# Connectors_Sch.net
KiCad netlist of a schematic drawn in Altium Designer
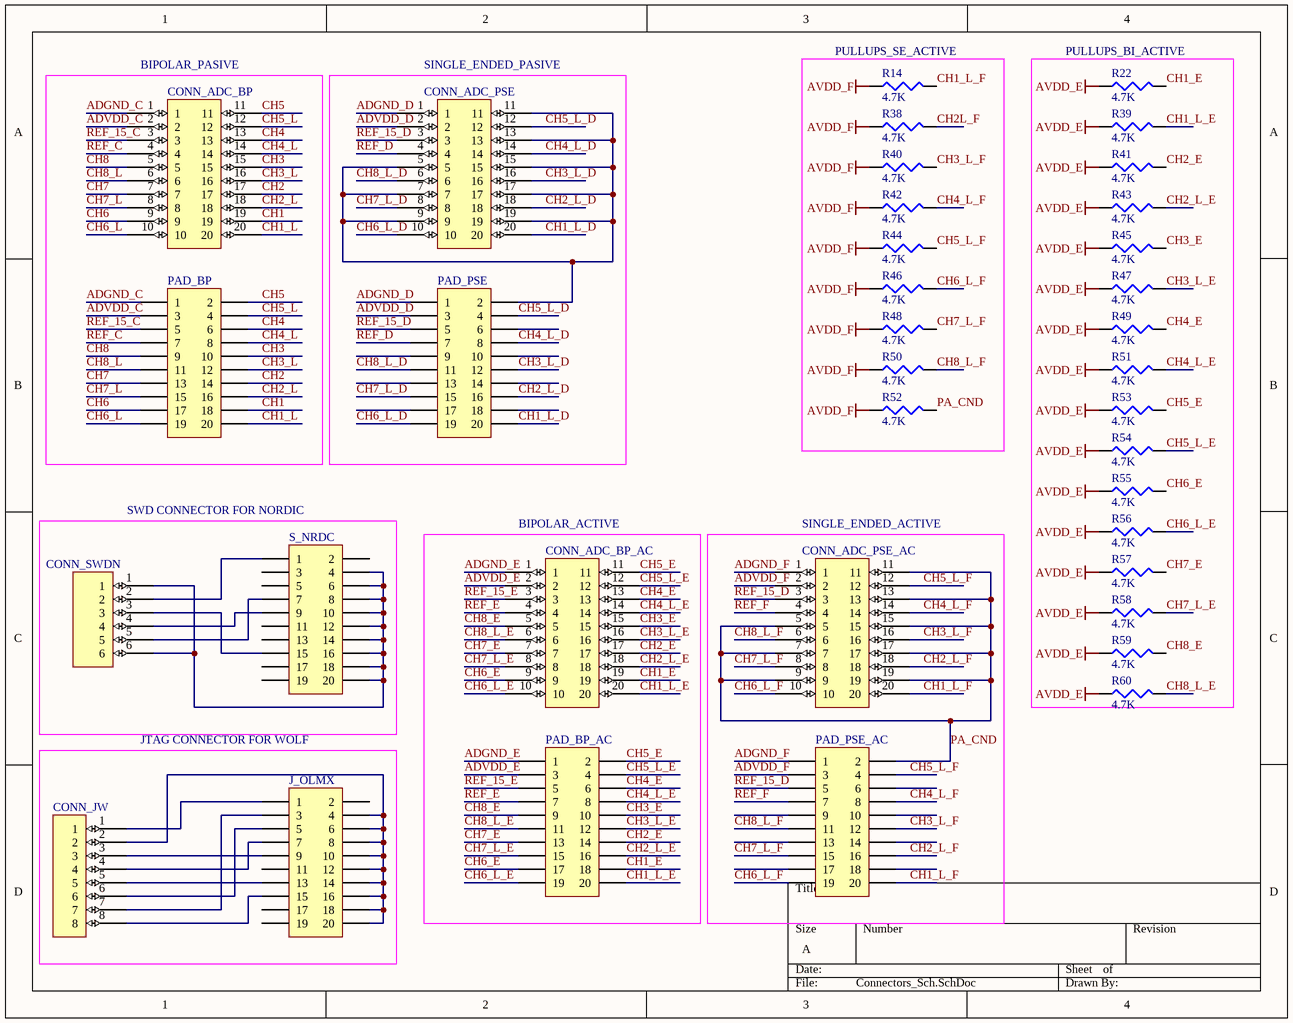
[diagram p0: Connectors_Sch.SchDoc]

(export (version "E")
  (design (tool "Eeschema 10.0.6"))
  (components
    (comp (ref "CONN_ADC_BP")
      (value "MOLEX_5051102091")
      (footprint "MOLEX_5051102091")
      (libsource (lib "Schlib1") (part "MOLEX_5051102091"))
    )
    (comp (ref "CONN_ADC_BP_AC")
      (value "MOLEX_5051102091")
      (footprint "MOLEX_5051102091")
      (libsource (lib "Schlib1") (part "MOLEX_5051102091"))
    )
    (comp (ref "CONN_ADC_PSE")
      (value "MOLEX_5051102091")
      (footprint "MOLEX_5051102091")
      (libsource (lib "Schlib1") (part "MOLEX_5051102091"))
    )
    (comp (ref "CONN_ADC_PSE_AC")
      (value "MOLEX_5051102091")
      (footprint "MOLEX_5051102091")
      (libsource (lib "Schlib1") (part "MOLEX_5051102091"))
    )
    (comp (ref "CONN_JW")
      (value "MOLEX_5051100892")
      (footprint "MOLEX_5051100892")
      (libsource (lib "Schlib1") (part "MOLEX_5051100892"))
    )
    (comp (ref "CONN_SWDN")
      (value "FFC & FPC Connectors 0.5 FPC ZIF BTM CONT EMBT PKG 6Ckt")
      (footprint "MOLEX_5051100692")
      (libsource (lib "Schlib2") (part "MOLEX_5051100692"))
    )
    (comp (ref "J_OLMX")
      (value "Header 10X2")
      (footprint "HDR2X10")
      (description "Header, 10-Pin, Dual row")
      (fields (field (name "PUBLISHER") "Altium Limited"))
      (libsource (lib "Miscellaneous Connectors") (part "Header 10X2"))
    )
    (comp (ref "PAD_BP")
      (value "Header 10X2")
      (footprint "HDR2X10")
      (description "Header, 10-Pin, Dual row")
      (fields (field (name "PUBLISHER") "Altium Limited"))
      (libsource (lib "Miscellaneous Connectors") (part "Header 10X2"))
    )
    (comp (ref "PAD_BP_AC")
      (value "Header 10X2")
      (footprint "HDR2X10")
      (description "Header, 10-Pin, Dual row")
      (fields (field (name "PUBLISHER") "Altium Limited"))
      (libsource (lib "Miscellaneous Connectors") (part "Header 10X2"))
    )
    (comp (ref "PAD_PSE")
      (value "Header 10X2")
      (footprint "HDR2X10")
      (description "Header, 10-Pin, Dual row")
      (fields (field (name "PUBLISHER") "Altium Limited"))
      (libsource (lib "Miscellaneous Connectors") (part "Header 10X2"))
    )
    (comp (ref "PAD_PSE_AC")
      (value "Header 10X2")
      (footprint "HDR2X10")
      (description "Header, 10-Pin, Dual row")
      (fields (field (name "PUBLISHER") "Altium Limited"))
      (libsource (lib "Miscellaneous Connectors") (part "Header 10X2"))
    )
    (comp (ref "R14")
      (value "4.7K")
      (footprint "0402")
      (description "Resistor")
      (fields (field (name "PUBLISHER") "Altium Limited"))
      (libsource (lib "Miscellaneous Devices") (part "Res3"))
    )
    (comp (ref "R22")
      (value "4.7K")
      (footprint "0402")
      (description "Resistor")
      (fields (field (name "PUBLISHER") "Altium Limited"))
      (libsource (lib "Miscellaneous Devices") (part "Res3"))
    )
    (comp (ref "R38")
      (value "4.7K")
      (footprint "0402")
      (description "Resistor")
      (fields (field (name "PUBLISHER") "Altium Limited"))
      (libsource (lib "Miscellaneous Devices") (part "Res3"))
    )
    (comp (ref "R39")
      (value "4.7K")
      (footprint "0402")
      (description "Resistor")
      (fields (field (name "PUBLISHER") "Altium Limited"))
      (libsource (lib "Miscellaneous Devices") (part "Res3"))
    )
    (comp (ref "R40")
      (value "4.7K")
      (footprint "0402")
      (description "Resistor")
      (fields (field (name "PUBLISHER") "Altium Limited"))
      (libsource (lib "Miscellaneous Devices") (part "Res3"))
    )
    (comp (ref "R41")
      (value "4.7K")
      (footprint "0402")
      (description "Resistor")
      (fields (field (name "PUBLISHER") "Altium Limited"))
      (libsource (lib "Miscellaneous Devices") (part "Res3"))
    )
    (comp (ref "R42")
      (value "4.7K")
      (footprint "0402")
      (description "Resistor")
      (fields (field (name "PUBLISHER") "Altium Limited"))
      (libsource (lib "Miscellaneous Devices") (part "Res3"))
    )
    (comp (ref "R43")
      (value "4.7K")
      (footprint "0402")
      (description "Resistor")
      (fields (field (name "PUBLISHER") "Altium Limited"))
      (libsource (lib "Miscellaneous Devices") (part "Res3"))
    )
    (comp (ref "R44")
      (value "4.7K")
      (footprint "0402")
      (description "Resistor")
      (fields (field (name "PUBLISHER") "Altium Limited"))
      (libsource (lib "Miscellaneous Devices") (part "Res3"))
    )
    (comp (ref "R45")
      (value "4.7K")
      (footprint "0402")
      (description "Resistor")
      (fields (field (name "PUBLISHER") "Altium Limited"))
      (libsource (lib "Miscellaneous Devices") (part "Res3"))
    )
    (comp (ref "R46")
      (value "4.7K")
      (footprint "0402")
      (description "Resistor")
      (fields (field (name "PUBLISHER") "Altium Limited"))
      (libsource (lib "Miscellaneous Devices") (part "Res3"))
    )
    (comp (ref "R47")
      (value "4.7K")
      (footprint "0402")
      (description "Resistor")
      (fields (field (name "PUBLISHER") "Altium Limited"))
      (libsource (lib "Miscellaneous Devices") (part "Res3"))
    )
    (comp (ref "R48")
      (value "4.7K")
      (footprint "0402")
      (description "Resistor")
      (fields (field (name "PUBLISHER") "Altium Limited"))
      (libsource (lib "Miscellaneous Devices") (part "Res3"))
    )
    (comp (ref "R49")
      (value "4.7K")
      (footprint "0402")
      (description "Resistor")
      (fields (field (name "PUBLISHER") "Altium Limited"))
      (libsource (lib "Miscellaneous Devices") (part "Res3"))
    )
    (comp (ref "R50")
      (value "4.7K")
      (footprint "0402")
      (description "Resistor")
      (fields (field (name "PUBLISHER") "Altium Limited"))
      (libsource (lib "Miscellaneous Devices") (part "Res3"))
    )
    (comp (ref "R51")
      (value "4.7K")
      (footprint "0402")
      (description "Resistor")
      (fields (field (name "PUBLISHER") "Altium Limited"))
      (libsource (lib "Miscellaneous Devices") (part "Res3"))
    )
    (comp (ref "R52")
      (value "4.7K")
      (footprint "0402")
      (description "Resistor")
      (fields (field (name "PUBLISHER") "Altium Limited"))
      (libsource (lib "Miscellaneous Devices") (part "Res3"))
    )
    (comp (ref "R53")
      (value "4.7K")
      (footprint "0402")
      (description "Resistor")
      (fields (field (name "PUBLISHER") "Altium Limited"))
      (libsource (lib "Miscellaneous Devices") (part "Res3"))
    )
    (comp (ref "R54")
      (value "4.7K")
      (footprint "0402")
      (description "Resistor")
      (fields (field (name "PUBLISHER") "Altium Limited"))
      (libsource (lib "Miscellaneous Devices") (part "Res3"))
    )
    (comp (ref "R55")
      (value "4.7K")
      (footprint "0402")
      (description "Resistor")
      (fields (field (name "PUBLISHER") "Altium Limited"))
      (libsource (lib "Miscellaneous Devices") (part "Res3"))
    )
    (comp (ref "R56")
      (value "4.7K")
      (footprint "0402")
      (description "Resistor")
      (fields (field (name "PUBLISHER") "Altium Limited"))
      (libsource (lib "Miscellaneous Devices") (part "Res3"))
    )
    (comp (ref "R57")
      (value "4.7K")
      (footprint "0402")
      (description "Resistor")
      (fields (field (name "PUBLISHER") "Altium Limited"))
      (libsource (lib "Miscellaneous Devices") (part "Res3"))
    )
    (comp (ref "R58")
      (value "4.7K")
      (footprint "0402")
      (description "Resistor")
      (fields (field (name "PUBLISHER") "Altium Limited"))
      (libsource (lib "Miscellaneous Devices") (part "Res3"))
    )
    (comp (ref "R59")
      (value "4.7K")
      (footprint "0402")
      (description "Resistor")
      (fields (field (name "PUBLISHER") "Altium Limited"))
      (libsource (lib "Miscellaneous Devices") (part "Res3"))
    )
    (comp (ref "R60")
      (value "4.7K")
      (footprint "0402")
      (description "Resistor")
      (fields (field (name "PUBLISHER") "Altium Limited"))
      (libsource (lib "Miscellaneous Devices") (part "Res3"))
    )
    (comp (ref "S_NRDC")
      (value "Header 10X2")
      (footprint "HDR2X10")
      (description "Header, 10-Pin, Dual row")
      (fields (field (name "PUBLISHER") "Altium Limited"))
      (libsource (lib "Miscellaneous Connectors") (part "Header 10X2"))
    )
  )
  (nets
    (net (code "1") (name "/ADGND_C") (class "Default")
      (node (ref "CONN_ADC_BP") (pin "1") (pinfunction "1_1") (pintype "bidirectional"))
      (node (ref "PAD_BP") (pin "1") (pinfunction "1_1") (pintype "passive"))
    )
    (net (code "2") (name "/ADGND_D") (class "Default")
      (node (ref "CONN_ADC_PSE") (pin "1") (pinfunction "1_1") (pintype "bidirectional"))
      (node (ref "PAD_PSE") (pin "1") (pinfunction "1_1") (pintype "passive"))
    )
    (net (code "3") (name "/ADGND_E") (class "Default")
      (node (ref "CONN_ADC_BP_AC") (pin "1") (pinfunction "1_1") (pintype "bidirectional"))
      (node (ref "PAD_BP_AC") (pin "1") (pinfunction "1_1") (pintype "passive"))
    )
    (net (code "4") (name "/ADGND_F") (class "Default")
      (node (ref "CONN_ADC_PSE_AC") (pin "1") (pinfunction "1_1") (pintype "bidirectional"))
      (node (ref "PAD_PSE_AC") (pin "1") (pinfunction "1_1") (pintype "passive"))
    )
    (net (code "5") (name "/ADVDD_C") (class "Default")
      (node (ref "CONN_ADC_BP") (pin "2") (pinfunction "2_2") (pintype "bidirectional"))
      (node (ref "PAD_BP") (pin "3") (pinfunction "3_3") (pintype "passive"))
    )
    (net (code "6") (name "/ADVDD_D") (class "Default")
      (node (ref "CONN_ADC_PSE") (pin "2") (pinfunction "2_2") (pintype "bidirectional"))
      (node (ref "PAD_PSE") (pin "3") (pinfunction "3_3") (pintype "passive"))
    )
    (net (code "7") (name "/ADVDD_E") (class "Default")
      (node (ref "CONN_ADC_BP_AC") (pin "2") (pinfunction "2_2") (pintype "bidirectional"))
      (node (ref "PAD_BP_AC") (pin "3") (pinfunction "3_3") (pintype "passive"))
    )
    (net (code "8") (name "/ADVDD_F") (class "Default")
      (node (ref "CONN_ADC_PSE_AC") (pin "2") (pinfunction "2_2") (pintype "bidirectional"))
      (node (ref "PAD_PSE_AC") (pin "3") (pinfunction "3_3") (pintype "passive"))
    )
    (net (code "9") (name "/CH1") (class "Default")
      (node (ref "CONN_ADC_BP") (pin "19") (pinfunction "19_19") (pintype "bidirectional"))
      (node (ref "PAD_BP") (pin "18") (pinfunction "18_18") (pintype "passive"))
    )
    (net (code "10") (name "/CH1_E") (class "Default")
      (node (ref "CONN_ADC_BP_AC") (pin "19") (pinfunction "19_19") (pintype "bidirectional"))
      (node (ref "PAD_BP_AC") (pin "18") (pinfunction "18_18") (pintype "passive"))
      (node (ref "R22") (pin "2") (pinfunction "2_2") (pintype "passive"))
    )
    (net (code "11") (name "/CH1_L") (class "Default")
      (node (ref "CONN_ADC_BP") (pin "20") (pinfunction "20_20") (pintype "bidirectional"))
      (node (ref "PAD_BP") (pin "20") (pinfunction "20_20") (pintype "passive"))
    )
    (net (code "12") (name "/CH1_L_D") (class "Default")
      (node (ref "CONN_ADC_PSE") (pin "20") (pinfunction "20_20") (pintype "bidirectional"))
      (node (ref "PAD_PSE") (pin "20") (pinfunction "20_20") (pintype "passive"))
    )
    (net (code "13") (name "/CH1_L_E") (class "Default")
      (node (ref "CONN_ADC_BP_AC") (pin "20") (pinfunction "20_20") (pintype "bidirectional"))
      (node (ref "PAD_BP_AC") (pin "20") (pinfunction "20_20") (pintype "passive"))
      (node (ref "R39") (pin "2") (pinfunction "2_2") (pintype "passive"))
    )
    (net (code "14") (name "/CH1_L_F") (class "Default")
      (node (ref "CONN_ADC_PSE_AC") (pin "20") (pinfunction "20_20") (pintype "bidirectional"))
      (node (ref "PAD_PSE_AC") (pin "20") (pinfunction "20_20") (pintype "passive"))
      (node (ref "R14") (pin "2") (pinfunction "2_2") (pintype "passive"))
    )
    (net (code "15") (name "/CH2") (class "Default")
      (node (ref "CONN_ADC_BP") (pin "17") (pinfunction "17_17") (pintype "bidirectional"))
      (node (ref "PAD_BP") (pin "14") (pinfunction "14_14") (pintype "passive"))
    )
    (net (code "16") (name "/CH2L_F") (class "Default")
      (node (ref "R38") (pin "2") (pinfunction "2_2") (pintype "passive"))
    )
    (net (code "17") (name "/CH2_E") (class "Default")
      (node (ref "CONN_ADC_BP_AC") (pin "17") (pinfunction "17_17") (pintype "bidirectional"))
      (node (ref "PAD_BP_AC") (pin "14") (pinfunction "14_14") (pintype "passive"))
      (node (ref "R41") (pin "2") (pinfunction "2_2") (pintype "passive"))
    )
    (net (code "18") (name "/CH2_L") (class "Default")
      (node (ref "CONN_ADC_BP") (pin "18") (pinfunction "18_18") (pintype "bidirectional"))
      (node (ref "PAD_BP") (pin "16") (pinfunction "16_16") (pintype "passive"))
    )
    (net (code "19") (name "/CH2_L_D") (class "Default")
      (node (ref "CONN_ADC_PSE") (pin "18") (pinfunction "18_18") (pintype "bidirectional"))
      (node (ref "PAD_PSE") (pin "16") (pinfunction "16_16") (pintype "passive"))
    )
    (net (code "20") (name "/CH2_L_E") (class "Default")
      (node (ref "CONN_ADC_BP_AC") (pin "18") (pinfunction "18_18") (pintype "bidirectional"))
      (node (ref "PAD_BP_AC") (pin "16") (pinfunction "16_16") (pintype "passive"))
      (node (ref "R43") (pin "2") (pinfunction "2_2") (pintype "passive"))
    )
    (net (code "21") (name "/CH2_L_F") (class "Default")
      (node (ref "CONN_ADC_PSE_AC") (pin "18") (pinfunction "18_18") (pintype "bidirectional"))
      (node (ref "PAD_PSE_AC") (pin "16") (pinfunction "16_16") (pintype "passive"))
    )
    (net (code "22") (name "/CH3") (class "Default")
      (node (ref "CONN_ADC_BP") (pin "15") (pinfunction "15_15") (pintype "bidirectional"))
      (node (ref "PAD_BP") (pin "10") (pinfunction "10_10") (pintype "passive"))
    )
    (net (code "23") (name "/CH3_E") (class "Default")
      (node (ref "CONN_ADC_BP_AC") (pin "15") (pinfunction "15_15") (pintype "bidirectional"))
      (node (ref "PAD_BP_AC") (pin "10") (pinfunction "10_10") (pintype "passive"))
      (node (ref "R45") (pin "2") (pinfunction "2_2") (pintype "passive"))
    )
    (net (code "24") (name "/CH3_L") (class "Default")
      (node (ref "CONN_ADC_BP") (pin "16") (pinfunction "16_16") (pintype "bidirectional"))
      (node (ref "PAD_BP") (pin "12") (pinfunction "12_12") (pintype "passive"))
    )
    (net (code "25") (name "/CH3_L_D") (class "Default")
      (node (ref "CONN_ADC_PSE") (pin "16") (pinfunction "16_16") (pintype "bidirectional"))
      (node (ref "PAD_PSE") (pin "12") (pinfunction "12_12") (pintype "passive"))
    )
    (net (code "26") (name "/CH3_L_E") (class "Default")
      (node (ref "CONN_ADC_BP_AC") (pin "16") (pinfunction "16_16") (pintype "bidirectional"))
      (node (ref "PAD_BP_AC") (pin "12") (pinfunction "12_12") (pintype "passive"))
      (node (ref "R47") (pin "2") (pinfunction "2_2") (pintype "passive"))
    )
    (net (code "27") (name "/CH3_L_F") (class "Default")
      (node (ref "CONN_ADC_PSE_AC") (pin "16") (pinfunction "16_16") (pintype "bidirectional"))
      (node (ref "PAD_PSE_AC") (pin "12") (pinfunction "12_12") (pintype "passive"))
      (node (ref "R40") (pin "2") (pinfunction "2_2") (pintype "passive"))
    )
    (net (code "28") (name "/CH4") (class "Default")
      (node (ref "CONN_ADC_BP") (pin "13") (pinfunction "13_13") (pintype "bidirectional"))
      (node (ref "PAD_BP") (pin "6") (pinfunction "6_6") (pintype "passive"))
    )
    (net (code "29") (name "/CH4_E") (class "Default")
      (node (ref "CONN_ADC_BP_AC") (pin "13") (pinfunction "13_13") (pintype "bidirectional"))
      (node (ref "PAD_BP_AC") (pin "6") (pinfunction "6_6") (pintype "passive"))
      (node (ref "R49") (pin "2") (pinfunction "2_2") (pintype "passive"))
    )
    (net (code "30") (name "/CH4_L") (class "Default")
      (node (ref "CONN_ADC_BP") (pin "14") (pinfunction "14_14") (pintype "bidirectional"))
      (node (ref "PAD_BP") (pin "8") (pinfunction "8_8") (pintype "passive"))
    )
    (net (code "31") (name "/CH4_L_D") (class "Default")
      (node (ref "CONN_ADC_PSE") (pin "14") (pinfunction "14_14") (pintype "bidirectional"))
      (node (ref "PAD_PSE") (pin "8") (pinfunction "8_8") (pintype "passive"))
    )
    (net (code "32") (name "/CH4_L_E") (class "Default")
      (node (ref "CONN_ADC_BP_AC") (pin "14") (pinfunction "14_14") (pintype "bidirectional"))
      (node (ref "PAD_BP_AC") (pin "8") (pinfunction "8_8") (pintype "passive"))
      (node (ref "R51") (pin "2") (pinfunction "2_2") (pintype "passive"))
    )
    (net (code "33") (name "/CH4_L_F") (class "Default")
      (node (ref "CONN_ADC_PSE_AC") (pin "14") (pinfunction "14_14") (pintype "bidirectional"))
      (node (ref "PAD_PSE_AC") (pin "8") (pinfunction "8_8") (pintype "passive"))
      (node (ref "R42") (pin "2") (pinfunction "2_2") (pintype "passive"))
    )
    (net (code "34") (name "/CH5") (class "Default")
      (node (ref "CONN_ADC_BP") (pin "11") (pinfunction "11_11") (pintype "bidirectional"))
      (node (ref "PAD_BP") (pin "2") (pinfunction "2_2") (pintype "passive"))
    )
    (net (code "35") (name "/CH5_E") (class "Default")
      (node (ref "CONN_ADC_BP_AC") (pin "11") (pinfunction "11_11") (pintype "bidirectional"))
      (node (ref "PAD_BP_AC") (pin "2") (pinfunction "2_2") (pintype "passive"))
      (node (ref "R53") (pin "2") (pinfunction "2_2") (pintype "passive"))
    )
    (net (code "36") (name "/CH5_L") (class "Default")
      (node (ref "CONN_ADC_BP") (pin "12") (pinfunction "12_12") (pintype "bidirectional"))
      (node (ref "PAD_BP") (pin "4") (pinfunction "4_4") (pintype "passive"))
    )
    (net (code "37") (name "/CH5_L_D") (class "Default")
      (node (ref "CONN_ADC_PSE") (pin "12") (pinfunction "12_12") (pintype "bidirectional"))
      (node (ref "PAD_PSE") (pin "4") (pinfunction "4_4") (pintype "passive"))
    )
    (net (code "38") (name "/CH5_L_E") (class "Default")
      (node (ref "CONN_ADC_BP_AC") (pin "12") (pinfunction "12_12") (pintype "bidirectional"))
      (node (ref "PAD_BP_AC") (pin "4") (pinfunction "4_4") (pintype "passive"))
      (node (ref "R54") (pin "2") (pinfunction "2_2") (pintype "passive"))
    )
    (net (code "39") (name "/CH5_L_F") (class "Default")
      (node (ref "CONN_ADC_PSE_AC") (pin "12") (pinfunction "12_12") (pintype "bidirectional"))
      (node (ref "PAD_PSE_AC") (pin "4") (pinfunction "4_4") (pintype "passive"))
      (node (ref "R44") (pin "2") (pinfunction "2_2") (pintype "passive"))
    )
    (net (code "40") (name "/CH6") (class "Default")
      (node (ref "CONN_ADC_BP") (pin "9") (pinfunction "9_9") (pintype "bidirectional"))
      (node (ref "PAD_BP") (pin "17") (pinfunction "17_17") (pintype "passive"))
    )
    (net (code "41") (name "/CH6_E") (class "Default")
      (node (ref "CONN_ADC_BP_AC") (pin "9") (pinfunction "9_9") (pintype "bidirectional"))
      (node (ref "PAD_BP_AC") (pin "17") (pinfunction "17_17") (pintype "passive"))
      (node (ref "R55") (pin "2") (pinfunction "2_2") (pintype "passive"))
    )
    (net (code "42") (name "/CH6_L") (class "Default")
      (node (ref "CONN_ADC_BP") (pin "10") (pinfunction "10_10") (pintype "bidirectional"))
      (node (ref "PAD_BP") (pin "19") (pinfunction "19_19") (pintype "passive"))
    )
    (net (code "43") (name "/CH6_L_D") (class "Default")
      (node (ref "CONN_ADC_PSE") (pin "10") (pinfunction "10_10") (pintype "bidirectional"))
      (node (ref "PAD_PSE") (pin "19") (pinfunction "19_19") (pintype "passive"))
    )
    (net (code "44") (name "/CH6_L_E") (class "Default")
      (node (ref "CONN_ADC_BP_AC") (pin "10") (pinfunction "10_10") (pintype "bidirectional"))
      (node (ref "PAD_BP_AC") (pin "19") (pinfunction "19_19") (pintype "passive"))
      (node (ref "R56") (pin "2") (pinfunction "2_2") (pintype "passive"))
    )
    (net (code "45") (name "/CH6_L_F") (class "Default")
      (node (ref "CONN_ADC_PSE_AC") (pin "10") (pinfunction "10_10") (pintype "bidirectional"))
      (node (ref "PAD_PSE_AC") (pin "19") (pinfunction "19_19") (pintype "passive"))
      (node (ref "R46") (pin "2") (pinfunction "2_2") (pintype "passive"))
    )
    (net (code "46") (name "/CH7") (class "Default")
      (node (ref "CONN_ADC_BP") (pin "7") (pinfunction "7_7") (pintype "bidirectional"))
      (node (ref "PAD_BP") (pin "13") (pinfunction "13_13") (pintype "passive"))
    )
    (net (code "47") (name "/CH7_E") (class "Default")
      (node (ref "CONN_ADC_BP_AC") (pin "7") (pinfunction "7_7") (pintype "bidirectional"))
      (node (ref "PAD_BP_AC") (pin "13") (pinfunction "13_13") (pintype "passive"))
      (node (ref "R57") (pin "2") (pinfunction "2_2") (pintype "passive"))
    )
    (net (code "48") (name "/CH7_L") (class "Default")
      (node (ref "CONN_ADC_BP") (pin "8") (pinfunction "8_8") (pintype "bidirectional"))
      (node (ref "PAD_BP") (pin "15") (pinfunction "15_15") (pintype "passive"))
    )
    (net (code "49") (name "/CH7_L_D") (class "Default")
      (node (ref "CONN_ADC_PSE") (pin "8") (pinfunction "8_8") (pintype "bidirectional"))
      (node (ref "PAD_PSE") (pin "15") (pinfunction "15_15") (pintype "passive"))
    )
    (net (code "50") (name "/CH7_L_E") (class "Default")
      (node (ref "CONN_ADC_BP_AC") (pin "8") (pinfunction "8_8") (pintype "bidirectional"))
      (node (ref "PAD_BP_AC") (pin "15") (pinfunction "15_15") (pintype "passive"))
      (node (ref "R58") (pin "2") (pinfunction "2_2") (pintype "passive"))
    )
    (net (code "51") (name "/CH7_L_F") (class "Default")
      (node (ref "CONN_ADC_PSE_AC") (pin "8") (pinfunction "8_8") (pintype "bidirectional"))
      (node (ref "PAD_PSE_AC") (pin "15") (pinfunction "15_15") (pintype "passive"))
      (node (ref "R48") (pin "2") (pinfunction "2_2") (pintype "passive"))
    )
    (net (code "52") (name "/CH8") (class "Default")
      (node (ref "CONN_ADC_BP") (pin "5") (pinfunction "5_5") (pintype "bidirectional"))
      (node (ref "PAD_BP") (pin "9") (pinfunction "9_9") (pintype "passive"))
    )
    (net (code "53") (name "/CH8_E") (class "Default")
      (node (ref "CONN_ADC_BP_AC") (pin "5") (pinfunction "5_5") (pintype "bidirectional"))
      (node (ref "PAD_BP_AC") (pin "9") (pinfunction "9_9") (pintype "passive"))
      (node (ref "R59") (pin "2") (pinfunction "2_2") (pintype "passive"))
    )
    (net (code "54") (name "/CH8_L") (class "Default")
      (node (ref "CONN_ADC_BP") (pin "6") (pinfunction "6_6") (pintype "bidirectional"))
      (node (ref "PAD_BP") (pin "11") (pinfunction "11_11") (pintype "passive"))
    )
    (net (code "55") (name "/CH8_L_D") (class "Default")
      (node (ref "CONN_ADC_PSE") (pin "6") (pinfunction "6_6") (pintype "bidirectional"))
      (node (ref "PAD_PSE") (pin "11") (pinfunction "11_11") (pintype "passive"))
    )
    (net (code "56") (name "/CH8_L_E") (class "Default")
      (node (ref "CONN_ADC_BP_AC") (pin "6") (pinfunction "6_6") (pintype "bidirectional"))
      (node (ref "PAD_BP_AC") (pin "11") (pinfunction "11_11") (pintype "passive"))
      (node (ref "R60") (pin "2") (pinfunction "2_2") (pintype "passive"))
    )
    (net (code "57") (name "/CH8_L_F") (class "Default")
      (node (ref "CONN_ADC_PSE_AC") (pin "6") (pinfunction "6_6") (pintype "bidirectional"))
      (node (ref "PAD_PSE_AC") (pin "11") (pinfunction "11_11") (pintype "passive"))
      (node (ref "R50") (pin "2") (pinfunction "2_2") (pintype "passive"))
    )
    (net (code "58") (name "/PA_CND") (class "Default")
      (node (ref "CONN_ADC_PSE_AC") (pin "11") (pinfunction "11_11") (pintype "bidirectional"))
      (node (ref "CONN_ADC_PSE_AC") (pin "13") (pinfunction "13_13") (pintype "bidirectional"))
      (node (ref "CONN_ADC_PSE_AC") (pin "15") (pinfunction "15_15") (pintype "bidirectional"))
      (node (ref "CONN_ADC_PSE_AC") (pin "17") (pinfunction "17_17") (pintype "bidirectional"))
      (node (ref "CONN_ADC_PSE_AC") (pin "19") (pinfunction "19_19") (pintype "bidirectional"))
      (node (ref "CONN_ADC_PSE_AC") (pin "5") (pinfunction "5_5") (pintype "bidirectional"))
      (node (ref "CONN_ADC_PSE_AC") (pin "7") (pinfunction "7_7") (pintype "bidirectional"))
      (node (ref "CONN_ADC_PSE_AC") (pin "9") (pinfunction "9_9") (pintype "bidirectional"))
      (node (ref "PAD_PSE_AC") (pin "2") (pinfunction "2_2") (pintype "passive"))
      (node (ref "R52") (pin "2") (pinfunction "2_2") (pintype "passive"))
    )
    (net (code "59") (name "/REF_15_C") (class "Default")
      (node (ref "CONN_ADC_BP") (pin "3") (pinfunction "3_3") (pintype "bidirectional"))
      (node (ref "PAD_BP") (pin "5") (pinfunction "5_5") (pintype "passive"))
    )
    (net (code "60") (name "/REF_15_D") (class "Default")
      (node (ref "CONN_ADC_PSE") (pin "3") (pinfunction "3_3") (pintype "bidirectional"))
      (node (ref "CONN_ADC_PSE_AC") (pin "3") (pinfunction "3_3") (pintype "bidirectional"))
      (node (ref "PAD_PSE") (pin "5") (pinfunction "5_5") (pintype "passive"))
      (node (ref "PAD_PSE_AC") (pin "5") (pinfunction "5_5") (pintype "passive"))
    )
    (net (code "61") (name "/REF_15_E") (class "Default")
      (node (ref "CONN_ADC_BP_AC") (pin "3") (pinfunction "3_3") (pintype "bidirectional"))
      (node (ref "PAD_BP_AC") (pin "5") (pinfunction "5_5") (pintype "passive"))
    )
    (net (code "62") (name "/REF_C") (class "Default")
      (node (ref "CONN_ADC_BP") (pin "4") (pinfunction "4_4") (pintype "bidirectional"))
      (node (ref "PAD_BP") (pin "7") (pinfunction "7_7") (pintype "passive"))
    )
    (net (code "63") (name "/REF_D") (class "Default")
      (node (ref "CONN_ADC_PSE") (pin "4") (pinfunction "4_4") (pintype "bidirectional"))
      (node (ref "PAD_PSE") (pin "7") (pinfunction "7_7") (pintype "passive"))
    )
    (net (code "64") (name "/REF_E") (class "Default")
      (node (ref "CONN_ADC_BP_AC") (pin "4") (pinfunction "4_4") (pintype "bidirectional"))
      (node (ref "PAD_BP_AC") (pin "7") (pinfunction "7_7") (pintype "passive"))
    )
    (net (code "65") (name "/REF_F") (class "Default")
      (node (ref "CONN_ADC_PSE_AC") (pin "4") (pinfunction "4_4") (pintype "bidirectional"))
      (node (ref "PAD_PSE_AC") (pin "7") (pinfunction "7_7") (pintype "passive"))
    )
    (net (code "66") (name "AVDD_E") (class "Default")
      (node (ref "R22") (pin "1") (pinfunction "1_1") (pintype "passive"))
      (node (ref "R39") (pin "1") (pinfunction "1_1") (pintype "passive"))
      (node (ref "R41") (pin "1") (pinfunction "1_1") (pintype "passive"))
      (node (ref "R43") (pin "1") (pinfunction "1_1") (pintype "passive"))
      (node (ref "R45") (pin "1") (pinfunction "1_1") (pintype "passive"))
      (node (ref "R47") (pin "1") (pinfunction "1_1") (pintype "passive"))
      (node (ref "R49") (pin "1") (pinfunction "1_1") (pintype "passive"))
      (node (ref "R51") (pin "1") (pinfunction "1_1") (pintype "passive"))
      (node (ref "R53") (pin "1") (pinfunction "1_1") (pintype "passive"))
      (node (ref "R54") (pin "1") (pinfunction "1_1") (pintype "passive"))
      (node (ref "R55") (pin "1") (pinfunction "1_1") (pintype "passive"))
      (node (ref "R56") (pin "1") (pinfunction "1_1") (pintype "passive"))
      (node (ref "R57") (pin "1") (pinfunction "1_1") (pintype "passive"))
      (node (ref "R58") (pin "1") (pinfunction "1_1") (pintype "passive"))
      (node (ref "R59") (pin "1") (pinfunction "1_1") (pintype "passive"))
      (node (ref "R60") (pin "1") (pinfunction "1_1") (pintype "passive"))
    )
    (net (code "67") (name "AVDD_F") (class "Default")
      (node (ref "R14") (pin "1") (pinfunction "1_1") (pintype "passive"))
      (node (ref "R38") (pin "1") (pinfunction "1_1") (pintype "passive"))
      (node (ref "R40") (pin "1") (pinfunction "1_1") (pintype "passive"))
      (node (ref "R42") (pin "1") (pinfunction "1_1") (pintype "passive"))
      (node (ref "R44") (pin "1") (pinfunction "1_1") (pintype "passive"))
      (node (ref "R46") (pin "1") (pinfunction "1_1") (pintype "passive"))
      (node (ref "R48") (pin "1") (pinfunction "1_1") (pintype "passive"))
      (node (ref "R50") (pin "1") (pinfunction "1_1") (pintype "passive"))
      (node (ref "R52") (pin "1") (pinfunction "1_1") (pintype "passive"))
    )
    (net (code "68") (name "Net-(CONN_ADC_PSE-Pad11)") (class "Default")
      (node (ref "CONN_ADC_PSE") (pin "11") (pinfunction "11_11") (pintype "bidirectional"))
      (node (ref "CONN_ADC_PSE") (pin "13") (pinfunction "13_13") (pintype "bidirectional"))
      (node (ref "CONN_ADC_PSE") (pin "15") (pinfunction "15_15") (pintype "bidirectional"))
      (node (ref "CONN_ADC_PSE") (pin "17") (pinfunction "17_17") (pintype "bidirectional"))
      (node (ref "CONN_ADC_PSE") (pin "19") (pinfunction "19_19") (pintype "bidirectional"))
      (node (ref "CONN_ADC_PSE") (pin "5") (pinfunction "5_5") (pintype "bidirectional"))
      (node (ref "CONN_ADC_PSE") (pin "7") (pinfunction "7_7") (pintype "bidirectional"))
      (node (ref "CONN_ADC_PSE") (pin "9") (pinfunction "9_9") (pintype "bidirectional"))
      (node (ref "PAD_PSE") (pin "2") (pinfunction "2_2") (pintype "passive"))
    )
    (net (code "69") (name "Net-(CONN_JW-Pad1)") (class "Default")
      (node (ref "CONN_JW") (pin "1") (pinfunction "1_1") (pintype "bidirectional"))
      (node (ref "J_OLMX") (pin "1") (pinfunction "1_1") (pintype "passive"))
    )
    (net (code "70") (name "Net-(CONN_JW-Pad2)") (class "Default")
      (node (ref "CONN_JW") (pin "2") (pinfunction "2_2") (pintype "bidirectional"))
      (node (ref "J_OLMX") (pin "10") (pinfunction "10_10") (pintype "passive"))
      (node (ref "J_OLMX") (pin "12") (pinfunction "12_12") (pintype "passive"))
      (node (ref "J_OLMX") (pin "14") (pinfunction "14_14") (pintype "passive"))
      (node (ref "J_OLMX") (pin "16") (pinfunction "16_16") (pintype "passive"))
      (node (ref "J_OLMX") (pin "18") (pinfunction "18_18") (pintype "passive"))
      (node (ref "J_OLMX") (pin "20") (pinfunction "20_20") (pintype "passive"))
      (node (ref "J_OLMX") (pin "4") (pinfunction "4_4") (pintype "passive"))
      (node (ref "J_OLMX") (pin "6") (pinfunction "6_6") (pintype "passive"))
      (node (ref "J_OLMX") (pin "8") (pinfunction "8_8") (pintype "passive"))
    )
    (net (code "71") (name "Net-(CONN_JW-Pad3)") (class "Default")
      (node (ref "CONN_JW") (pin "3") (pinfunction "3_3") (pintype "bidirectional"))
      (node (ref "J_OLMX") (pin "9") (pinfunction "9_9") (pintype "passive"))
    )
    (net (code "72") (name "Net-(CONN_JW-Pad4)") (class "Default")
      (node (ref "CONN_JW") (pin "4") (pinfunction "4_4") (pintype "bidirectional"))
      (node (ref "J_OLMX") (pin "7") (pinfunction "7_7") (pintype "passive"))
    )
    (net (code "73") (name "Net-(CONN_JW-Pad5)") (class "Default")
      (node (ref "CONN_JW") (pin "5") (pinfunction "5_5") (pintype "bidirectional"))
      (node (ref "J_OLMX") (pin "13") (pinfunction "13_13") (pintype "passive"))
    )
    (net (code "74") (name "Net-(CONN_JW-Pad6)") (class "Default")
      (node (ref "CONN_JW") (pin "6") (pinfunction "6_6") (pintype "bidirectional"))
      (node (ref "J_OLMX") (pin "5") (pinfunction "5_5") (pintype "passive"))
    )
    (net (code "75") (name "Net-(CONN_JW-Pad7)") (class "Default")
      (node (ref "CONN_JW") (pin "7") (pinfunction "7_7") (pintype "bidirectional"))
      (node (ref "J_OLMX") (pin "3") (pinfunction "3_3") (pintype "passive"))
    )
    (net (code "76") (name "Net-(CONN_JW-Pad8)") (class "Default")
      (node (ref "CONN_JW") (pin "8") (pinfunction "8_8") (pintype "bidirectional"))
      (node (ref "J_OLMX") (pin "15") (pinfunction "15_15") (pintype "passive"))
    )
    (net (code "77") (name "Net-(CONN_SWDN-Pad1)") (class "Default")
      (node (ref "CONN_SWDN") (pin "1") (pinfunction "1_1") (pintype "bidirectional"))
      (node (ref "CONN_SWDN") (pin "6") (pinfunction "6_6") (pintype "bidirectional"))
      (node (ref "S_NRDC") (pin "10") (pinfunction "10_10") (pintype "passive"))
      (node (ref "S_NRDC") (pin "12") (pinfunction "12_12") (pintype "passive"))
      (node (ref "S_NRDC") (pin "14") (pinfunction "14_14") (pintype "passive"))
      (node (ref "S_NRDC") (pin "16") (pinfunction "16_16") (pintype "passive"))
      (node (ref "S_NRDC") (pin "18") (pinfunction "18_18") (pintype "passive"))
      (node (ref "S_NRDC") (pin "20") (pinfunction "20_20") (pintype "passive"))
      (node (ref "S_NRDC") (pin "4") (pinfunction "4_4") (pintype "passive"))
      (node (ref "S_NRDC") (pin "6") (pinfunction "6_6") (pintype "passive"))
      (node (ref "S_NRDC") (pin "8") (pinfunction "8_8") (pintype "passive"))
    )
    (net (code "78") (name "Net-(CONN_SWDN-Pad2)") (class "Default")
      (node (ref "CONN_SWDN") (pin "2") (pinfunction "2_2") (pintype "bidirectional"))
      (node (ref "S_NRDC") (pin "1") (pinfunction "1_1") (pintype "passive"))
    )
    (net (code "79") (name "Net-(CONN_SWDN-Pad3)") (class "Default")
      (node (ref "CONN_SWDN") (pin "3") (pinfunction "3_3") (pintype "bidirectional"))
      (node (ref "S_NRDC") (pin "15") (pinfunction "15_15") (pintype "passive"))
    )
    (net (code "80") (name "Net-(CONN_SWDN-Pad4)") (class "Default")
      (node (ref "CONN_SWDN") (pin "4") (pinfunction "4_4") (pintype "bidirectional"))
      (node (ref "S_NRDC") (pin "9") (pinfunction "9_9") (pintype "passive"))
    )
    (net (code "81") (name "Net-(CONN_SWDN-Pad5)") (class "Default")
      (node (ref "CONN_SWDN") (pin "5") (pinfunction "5_5") (pintype "bidirectional"))
      (node (ref "S_NRDC") (pin "7") (pinfunction "7_7") (pintype "passive"))
    )
    (net (code "82") (name "unconnected-(J_OLMX-Pad2)") (class "Default")
      (node (ref "J_OLMX") (pin "2") (pinfunction "2_2") (pintype "passive"))
    )
    (net (code "83") (name "unconnected-(J_OLMX-Pad11)") (class "Default")
      (node (ref "J_OLMX") (pin "11") (pinfunction "11_11") (pintype "passive"))
    )
    (net (code "84") (name "unconnected-(J_OLMX-Pad17)") (class "Default")
      (node (ref "J_OLMX") (pin "17") (pinfunction "17_17") (pintype "passive"))
    )
    (net (code "85") (name "unconnected-(J_OLMX-Pad19)") (class "Default")
      (node (ref "J_OLMX") (pin "19") (pinfunction "19_19") (pintype "passive"))
    )
    (net (code "86") (name "unconnected-(PAD_PSE-Pad6)") (class "Default")
      (node (ref "PAD_PSE") (pin "6") (pinfunction "6_6") (pintype "passive"))
    )
    (net (code "87") (name "unconnected-(PAD_PSE-Pad9)") (class "Default")
      (node (ref "PAD_PSE") (pin "9") (pinfunction "9_9") (pintype "passive"))
    )
    (net (code "88") (name "unconnected-(PAD_PSE-Pad10)") (class "Default")
      (node (ref "PAD_PSE") (pin "10") (pinfunction "10_10") (pintype "passive"))
    )
    (net (code "89") (name "unconnected-(PAD_PSE-Pad13)") (class "Default")
      (node (ref "PAD_PSE") (pin "13") (pinfunction "13_13") (pintype "passive"))
    )
    (net (code "90") (name "unconnected-(PAD_PSE-Pad14)") (class "Default")
      (node (ref "PAD_PSE") (pin "14") (pinfunction "14_14") (pintype "passive"))
    )
    (net (code "91") (name "unconnected-(PAD_PSE-Pad17)") (class "Default")
      (node (ref "PAD_PSE") (pin "17") (pinfunction "17_17") (pintype "passive"))
    )
    (net (code "92") (name "unconnected-(PAD_PSE-Pad18)") (class "Default")
      (node (ref "PAD_PSE") (pin "18") (pinfunction "18_18") (pintype "passive"))
    )
    (net (code "93") (name "unconnected-(PAD_PSE_AC-Pad6)") (class "Default")
      (node (ref "PAD_PSE_AC") (pin "6") (pinfunction "6_6") (pintype "passive"))
    )
    (net (code "94") (name "unconnected-(PAD_PSE_AC-Pad9)") (class "Default")
      (node (ref "PAD_PSE_AC") (pin "9") (pinfunction "9_9") (pintype "passive"))
    )
    (net (code "95") (name "unconnected-(PAD_PSE_AC-Pad10)") (class "Default")
      (node (ref "PAD_PSE_AC") (pin "10") (pinfunction "10_10") (pintype "passive"))
    )
    (net (code "96") (name "unconnected-(PAD_PSE_AC-Pad13)") (class "Default")
      (node (ref "PAD_PSE_AC") (pin "13") (pinfunction "13_13") (pintype "passive"))
    )
    (net (code "97") (name "unconnected-(PAD_PSE_AC-Pad14)") (class "Default")
      (node (ref "PAD_PSE_AC") (pin "14") (pinfunction "14_14") (pintype "passive"))
    )
    (net (code "98") (name "unconnected-(PAD_PSE_AC-Pad17)") (class "Default")
      (node (ref "PAD_PSE_AC") (pin "17") (pinfunction "17_17") (pintype "passive"))
    )
    (net (code "99") (name "unconnected-(PAD_PSE_AC-Pad18)") (class "Default")
      (node (ref "PAD_PSE_AC") (pin "18") (pinfunction "18_18") (pintype "passive"))
    )
    (net (code "100") (name "unconnected-(S_NRDC-Pad2)") (class "Default")
      (node (ref "S_NRDC") (pin "2") (pinfunction "2_2") (pintype "passive"))
    )
    (net (code "101") (name "unconnected-(S_NRDC-Pad3)") (class "Default")
      (node (ref "S_NRDC") (pin "3") (pinfunction "3_3") (pintype "passive"))
    )
    (net (code "102") (name "unconnected-(S_NRDC-Pad5)") (class "Default")
      (node (ref "S_NRDC") (pin "5") (pinfunction "5_5") (pintype "passive"))
    )
    (net (code "103") (name "unconnected-(S_NRDC-Pad11)") (class "Default")
      (node (ref "S_NRDC") (pin "11") (pinfunction "11_11") (pintype "passive"))
    )
    (net (code "104") (name "unconnected-(S_NRDC-Pad13)") (class "Default")
      (node (ref "S_NRDC") (pin "13") (pinfunction "13_13") (pintype "passive"))
    )
    (net (code "105") (name "unconnected-(S_NRDC-Pad17)") (class "Default")
      (node (ref "S_NRDC") (pin "17") (pinfunction "17_17") (pintype "passive"))
    )
    (net (code "106") (name "unconnected-(S_NRDC-Pad19)") (class "Default")
      (node (ref "S_NRDC") (pin "19") (pinfunction "19_19") (pintype "passive"))
    )
  )
)
